# DmxAnalogLed.net
KiCad netlist of a schematic drawn in EAGLE
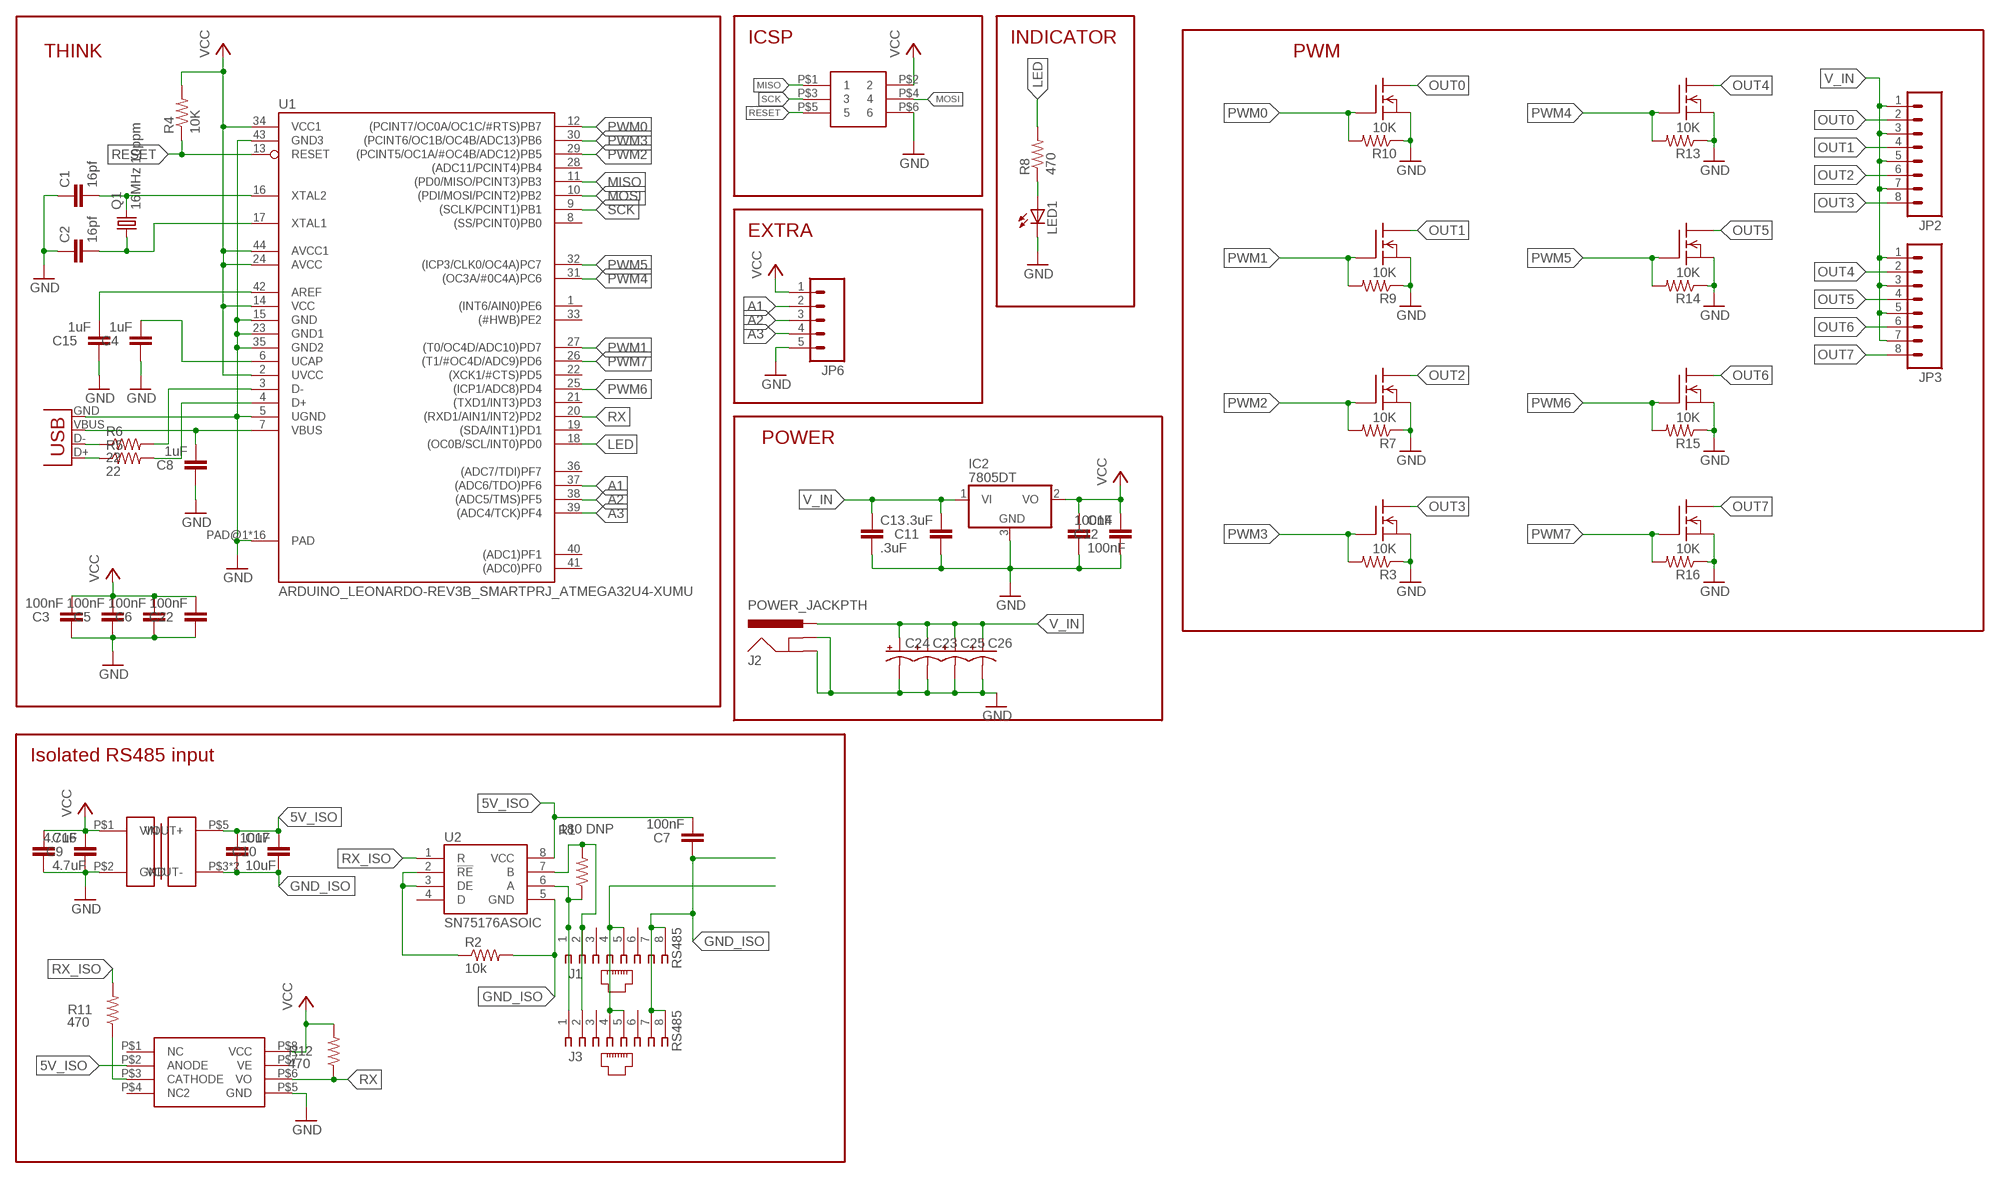
[diagram p0: schematic, sheet 1]

(export (version "E")
  (design (tool "Eeschema 10.0.6"))
  (components
    (comp (ref "C1")
      (value "16pf")
      (footprint "eagle-import:0805")
      (libsource (lib "eagle-import") (part "CAP0805"))
    )
    (comp (ref "C2")
      (value "16pf")
      (footprint "eagle-import:0805")
      (libsource (lib "eagle-import") (part "CAP0805"))
    )
    (comp (ref "C3")
      (value "100nF")
      (footprint "eagle-import:0805")
      (libsource (lib "eagle-import") (part "CAP0805"))
    )
    (comp (ref "C4")
      (value "1uF")
      (footprint "eagle-import:0805")
      (libsource (lib "eagle-import") (part "CAP0805"))
    )
    (comp (ref "C5")
      (value "100nF")
      (footprint "eagle-import:0805")
      (libsource (lib "eagle-import") (part "CAP0805"))
    )
    (comp (ref "C6")
      (value "100nF")
      (footprint "eagle-import:0805")
      (libsource (lib "eagle-import") (part "CAP0805"))
    )
    (comp (ref "C7")
      (value "100nF")
      (footprint "eagle-import:0805")
      (libsource (lib "eagle-import") (part "CAP0805"))
    )
    (comp (ref "C8")
      (value "1uF")
      (footprint "eagle-import:0805")
      (libsource (lib "eagle-import") (part "CAP0805"))
    )
    (comp (ref "C9")
      (value "4.7uF")
      (footprint "eagle-import:0805")
      (libsource (lib "eagle-import") (part "CAP0805"))
    )
    (comp (ref "C10")
      (value "10uF")
      (footprint "eagle-import:0805")
      (libsource (lib "eagle-import") (part "CAP0805"))
    )
    (comp (ref "C11")
      (value ".3uF")
      (footprint "eagle-import:0805")
      (libsource (lib "eagle-import") (part "CAP0805"))
    )
    (comp (ref "C12")
      (value "100nF")
      (footprint "eagle-import:0805")
      (libsource (lib "eagle-import") (part "CAP0805"))
    )
    (comp (ref "C13")
      (value ".3uF")
      (footprint "eagle-import:1210")
      (libsource (lib "eagle-import") (part "CAP1210"))
    )
    (comp (ref "C14")
      (value "100nF")
      (footprint "eagle-import:1210")
      (libsource (lib "eagle-import") (part "CAP1210"))
    )
    (comp (ref "C15")
      (value "1uF")
      (footprint "eagle-import:0805")
      (libsource (lib "eagle-import") (part "CAP0805"))
    )
    (comp (ref "C16")
      (value "4.7uF")
      (footprint "eagle-import:1210")
      (libsource (lib "eagle-import") (part "CAP1210"))
    )
    (comp (ref "C17")
      (value "10uF")
      (footprint "eagle-import:1210")
      (libsource (lib "eagle-import") (part "CAP1210"))
    )
    (comp (ref "C22")
      (value "100nF")
      (footprint "eagle-import:0805")
      (libsource (lib "eagle-import") (part "CAP0805"))
    )
    (comp (ref "C23")
      (value "CAP_POLE")
      (footprint "eagle-import:PANASONIC_E")
      (libsource (lib "eagle-import") (part "CAP_POLE"))
    )
    (comp (ref "C24")
      (value "CAP_POLE")
      (footprint "eagle-import:PANASONIC_E")
      (libsource (lib "eagle-import") (part "CAP_POLE"))
    )
    (comp (ref "C25")
      (value "CAP_POLE")
      (footprint "eagle-import:PANASONIC_E")
      (libsource (lib "eagle-import") (part "CAP_POLE"))
    )
    (comp (ref "C26")
      (value "CAP_POLE")
      (footprint "eagle-import:PANASONIC_E")
      (libsource (lib "eagle-import") (part "CAP_POLE"))
    )
    (comp (ref "IC2")
      (value "7805DT")
      (footprint "eagle-import:TO252")
      (libsource (lib "eagle-import") (part "78DT05"))
    )
    (comp (ref "J1")
      (value "RS485")
      (footprint "eagle-import:520426-4")
      (libsource (lib "eagle-import") (part "520426-4"))
    )
    (comp (ref "J2")
      (value "POWER_JACKPTH")
      (footprint "eagle-import:POWER_JACK_PTH")
      (libsource (lib "eagle-import") (part "POWER_JACKPTH"))
    )
    (comp (ref "J3")
      (value "RS485")
      (footprint "eagle-import:520426-4")
      (libsource (lib "eagle-import") (part "520426-4"))
    )
    (comp (ref "JP2")
      (value "M083.5MM-8")
      (footprint "eagle-import:SCREWTERMINAL-3.5MM-8")
      (libsource (lib "eagle-import") (part "M083.5MM-8"))
    )
    (comp (ref "JP3")
      (value "M083.5MM-8")
      (footprint "eagle-import:SCREWTERMINAL-3.5MM-8")
      (libsource (lib "eagle-import") (part "M083.5MM-8"))
    )
    (comp (ref "JP6")
      (value "M05PTH")
      (footprint "eagle-import:1X05")
      (libsource (lib "eagle-import") (part "M05PTH"))
    )
    (comp (ref "LED1")
      (value "LED5MM")
      (footprint "eagle-import:LED5MM")
      (libsource (lib "eagle-import") (part "LED5MM"))
    )
    (comp (ref "Q1")
      (value "16MHz 10ppm")
      (footprint "eagle-import:XS3225")
      (libsource (lib "eagle-import") (part "CRYSTAL"))
    )
    (comp (ref "R1")
      (value "180 DNP")
      (footprint "eagle-import:0805")
      (libsource (lib "eagle-import") (part "RESISTOR"))
    )
    (comp (ref "R2")
      (value "10k")
      (footprint "eagle-import:0805")
      (libsource (lib "eagle-import") (part "RESISTOR"))
    )
    (comp (ref "R3")
      (value "10K")
      (footprint "eagle-import:0805")
      (libsource (lib "eagle-import") (part "RESISTOR"))
    )
    (comp (ref "R4")
      (value "10K")
      (footprint "eagle-import:0805")
      (libsource (lib "eagle-import") (part "RESISTOR"))
    )
    (comp (ref "R5")
      (value "22")
      (footprint "eagle-import:0805")
      (libsource (lib "eagle-import") (part "RESISTOR"))
    )
    (comp (ref "R6")
      (value "22")
      (footprint "eagle-import:0805")
      (libsource (lib "eagle-import") (part "RESISTOR"))
    )
    (comp (ref "R7")
      (value "10K")
      (footprint "eagle-import:0805")
      (libsource (lib "eagle-import") (part "RESISTOR"))
    )
    (comp (ref "R8")
      (value "470")
      (footprint "eagle-import:0805")
      (libsource (lib "eagle-import") (part "RESISTOR"))
    )
    (comp (ref "R9")
      (value "10K")
      (footprint "eagle-import:0805")
      (libsource (lib "eagle-import") (part "RESISTOR"))
    )
    (comp (ref "R10")
      (value "10K")
      (footprint "eagle-import:0805")
      (libsource (lib "eagle-import") (part "RESISTOR"))
    )
    (comp (ref "R11")
      (value "470")
      (footprint "eagle-import:0805")
      (libsource (lib "eagle-import") (part "RESISTOR"))
    )
    (comp (ref "R12")
      (value "470")
      (footprint "eagle-import:0805")
      (libsource (lib "eagle-import") (part "RESISTOR"))
    )
    (comp (ref "R13")
      (value "10K")
      (footprint "eagle-import:0805")
      (libsource (lib "eagle-import") (part "RESISTOR"))
    )
    (comp (ref "R14")
      (value "10K")
      (footprint "eagle-import:0805")
      (libsource (lib "eagle-import") (part "RESISTOR"))
    )
    (comp (ref "R15")
      (value "10K")
      (footprint "eagle-import:0805")
      (libsource (lib "eagle-import") (part "RESISTOR"))
    )
    (comp (ref "R16")
      (value "10K")
      (footprint "eagle-import:0805")
      (libsource (lib "eagle-import") (part "RESISTOR"))
    )
    (comp (ref "U$1")
      (value "N_MOSFET")
      (footprint "eagle-import:TO252")
      (libsource (lib "eagle-import") (part "N_MOSFET"))
    )
    (comp (ref "U$2")
      (value "2X3HEADER")
      (footprint "eagle-import:2X3HEADER")
      (libsource (lib "eagle-import") (part "2X3HEADER"))
    )
    (comp (ref "U$3")
      (value "N_MOSFET")
      (footprint "eagle-import:TO252")
      (libsource (lib "eagle-import") (part "N_MOSFET"))
    )
    (comp (ref "U$4")
      (value "N_MOSFET")
      (footprint "eagle-import:TO252")
      (libsource (lib "eagle-import") (part "N_MOSFET"))
    )
    (comp (ref "U$5")
      (value "N_MOSFET")
      (footprint "eagle-import:TO252")
      (libsource (lib "eagle-import") (part "N_MOSFET"))
    )
    (comp (ref "U$6")
      (value "N_MOSFET")
      (footprint "eagle-import:TO252")
      (libsource (lib "eagle-import") (part "N_MOSFET"))
    )
    (comp (ref "U$7")
      (value "N_MOSFET")
      (footprint "eagle-import:TO252")
      (libsource (lib "eagle-import") (part "N_MOSFET"))
    )
    (comp (ref "U$8")
      (value "N_MOSFET")
      (footprint "eagle-import:TO252")
      (libsource (lib "eagle-import") (part "N_MOSFET"))
    )
    (comp (ref "U$9")
      (value "N_MOSFET")
      (footprint "eagle-import:TO252")
      (libsource (lib "eagle-import") (part "N_MOSFET"))
    )
    (comp (ref "U$10")
      (value "DC_DC_ISOLATED_0505")
      (footprint "eagle-import:IB_XLS-1W")
      (libsource (lib "eagle-import") (part "DC_DC_ISOLATED_0505"))
    )
    (comp (ref "U$12")
      (value "6N137")
      (footprint "eagle-import:8_SOIC")
      (libsource (lib "eagle-import") (part "6N137"))
    )
    (comp (ref "U1")
      (value "ARDUINO_LEONARDO-REV3B_SMARTPRJ_ATMEGA32U4-XUMU")
      (footprint "eagle-import:ARDUINO_LEONARDO-REV3B_SMARTPRJ_QFN44ML7X7")
      (libsource (lib "eagle-import") (part "ARDUINO_LEONARDO-REV3B_SMARTPRJ_ATMEGA32U4-XUMU"))
    )
    (comp (ref "U2")
      (value "SN75176ASOIC")
      (footprint "eagle-import:SO08")
      (libsource (lib "eagle-import") (part "SN75176ASOIC"))
    )
    (comp (ref "X1")
      (value "USBPTH")
      (footprint "eagle-import:USB-B-PTH")
      (libsource (lib "eagle-import") (part "USBPTH"))
    )
  )
  (nets
    (net (code "1") (name "5V_ISO") (class "Default")
      (node (ref "C10") (pin "2") (pinfunction "2_2") (pintype "passive"))
      (node (ref "C17") (pin "1") (pinfunction "1_1") (pintype "passive"))
      (node (ref "C7") (pin "2") (pinfunction "2_2") (pintype "passive"))
      (node (ref "U$10") (pin "P$5") (pinfunction "VOUT+_P$5") (pintype "power_in"))
      (node (ref "U$12") (pin "P$2") (pinfunction "ANODE_P$2") (pintype "bidirectional"))
      (node (ref "U2") (pin "8") (pinfunction "VCC_8") (pintype "bidirectional"))
    )
    (net (code "2") (name "A1") (class "Default")
      (node (ref "JP6") (pin "2") (pinfunction "2_2") (pintype "passive"))
      (node (ref "U1") (pin "37") (pinfunction "(ADC6/TDO)PF6_37") (pintype "bidirectional"))
    )
    (net (code "3") (name "A2") (class "Default")
      (node (ref "JP6") (pin "3") (pinfunction "3_3") (pintype "passive"))
      (node (ref "U1") (pin "38") (pinfunction "(ADC5/TMS)PF5_38") (pintype "bidirectional"))
    )
    (net (code "4") (name "A3") (class "Default")
      (node (ref "JP6") (pin "4") (pinfunction "4_4") (pintype "passive"))
      (node (ref "U1") (pin "39") (pinfunction "(ADC4/TCK)PF4_39") (pintype "bidirectional"))
    )
    (net (code "5") (name "GND") (class "Default")
      (node (ref "C1") (pin "1") (pinfunction "1_1") (pintype "passive"))
      (node (ref "C11") (pin "1") (pinfunction "1_1") (pintype "passive"))
      (node (ref "C12") (pin "1") (pinfunction "1_1") (pintype "passive"))
      (node (ref "C13") (pin "2") (pinfunction "2_2") (pintype "passive"))
      (node (ref "C14") (pin "2") (pinfunction "2_2") (pintype "passive"))
      (node (ref "C15") (pin "1") (pinfunction "1_1") (pintype "passive"))
      (node (ref "C16") (pin "2") (pinfunction "2_2") (pintype "passive"))
      (node (ref "C2") (pin "1") (pinfunction "1_1") (pintype "passive"))
      (node (ref "C22") (pin "1") (pinfunction "1_1") (pintype "passive"))
      (node (ref "C23") (pin "-") (pinfunction "-_-") (pintype "passive"))
      (node (ref "C24") (pin "-") (pinfunction "-_-") (pintype "passive"))
      (node (ref "C25") (pin "-") (pinfunction "-_-") (pintype "passive"))
      (node (ref "C26") (pin "-") (pinfunction "-_-") (pintype "passive"))
      (node (ref "C3") (pin "1") (pinfunction "1_1") (pintype "passive"))
      (node (ref "C4") (pin "1") (pinfunction "1_1") (pintype "passive"))
      (node (ref "C5") (pin "1") (pinfunction "1_1") (pintype "passive"))
      (node (ref "C6") (pin "1") (pinfunction "1_1") (pintype "passive"))
      (node (ref "C8") (pin "1") (pinfunction "1_1") (pintype "passive"))
      (node (ref "C9") (pin "1") (pinfunction "1_1") (pintype "passive"))
      (node (ref "IC2") (pin "3") (pinfunction "GND_3") (pintype "passive"))
      (node (ref "J2") (pin "GND") (pinfunction "GND_GND") (pintype "bidirectional"))
      (node (ref "J2") (pin "GNDBREAK") (pinfunction "GNDBREAK_GNDBREAK") (pintype "bidirectional"))
      (node (ref "JP6") (pin "5") (pinfunction "5_5") (pintype "passive"))
      (node (ref "LED1") (pin "K") (pinfunction "C_K") (pintype "passive"))
      (node (ref "R10") (pin "1") (pinfunction "1_1") (pintype "passive"))
      (node (ref "R13") (pin "1") (pinfunction "1_1") (pintype "passive"))
      (node (ref "R14") (pin "1") (pinfunction "1_1") (pintype "passive"))
      (node (ref "R15") (pin "1") (pinfunction "1_1") (pintype "passive"))
      (node (ref "R16") (pin "1") (pinfunction "1_1") (pintype "passive"))
      (node (ref "R3") (pin "1") (pinfunction "1_1") (pintype "passive"))
      (node (ref "R7") (pin "1") (pinfunction "1_1") (pintype "passive"))
      (node (ref "R9") (pin "1") (pinfunction "1_1") (pintype "passive"))
      (node (ref "U$1") (pin "P$2") (pinfunction "S_P$2") (pintype "bidirectional"))
      (node (ref "U$10") (pin "P$2") (pinfunction "GND_P$2") (pintype "power_in"))
      (node (ref "U$12") (pin "P$5") (pinfunction "GND_P$5") (pintype "bidirectional"))
      (node (ref "U$2") (pin "P$6") (pinfunction "6_P$6") (pintype "bidirectional"))
      (node (ref "U$3") (pin "P$2") (pinfunction "S_P$2") (pintype "bidirectional"))
      (node (ref "U$4") (pin "P$2") (pinfunction "S_P$2") (pintype "bidirectional"))
      (node (ref "U$5") (pin "P$2") (pinfunction "S_P$2") (pintype "bidirectional"))
      (node (ref "U$6") (pin "P$2") (pinfunction "S_P$2") (pintype "bidirectional"))
      (node (ref "U$7") (pin "P$2") (pinfunction "S_P$2") (pintype "bidirectional"))
      (node (ref "U$8") (pin "P$2") (pinfunction "S_P$2") (pintype "bidirectional"))
      (node (ref "U$9") (pin "P$2") (pinfunction "S_P$2") (pintype "bidirectional"))
      (node (ref "U1") (pin "15") (pinfunction "GND_15") (pintype "power_in"))
      (node (ref "U1") (pin "23") (pinfunction "GND1_23") (pintype "power_in"))
      (node (ref "U1") (pin "35") (pinfunction "GND2_35") (pintype "power_in"))
      (node (ref "U1") (pin "43") (pinfunction "GND3_43") (pintype "power_in"))
      (node (ref "U1") (pin "5") (pinfunction "UGND_5") (pintype "power_in"))
      (node (ref "U1") (pin "PAD@1") (pinfunction "PAD_PAD@1") (pintype "power_in"))
      (node (ref "U1") (pin "PAD@10") (pinfunction "PAD_PAD@10") (pintype "power_in"))
      (node (ref "U1") (pin "PAD@11") (pinfunction "PAD_PAD@11") (pintype "power_in"))
      (node (ref "U1") (pin "PAD@12") (pinfunction "PAD_PAD@12") (pintype "power_in"))
      (node (ref "U1") (pin "PAD@13") (pinfunction "PAD_PAD@13") (pintype "power_in"))
      (node (ref "U1") (pin "PAD@14") (pinfunction "PAD_PAD@14") (pintype "power_in"))
      (node (ref "U1") (pin "PAD@15") (pinfunction "PAD_PAD@15") (pintype "power_in"))
      (node (ref "U1") (pin "PAD@16") (pinfunction "PAD_PAD@16") (pintype "power_in"))
      (node (ref "U1") (pin "PAD@2") (pinfunction "PAD_PAD@2") (pintype "power_in"))
      (node (ref "U1") (pin "PAD@3") (pinfunction "PAD_PAD@3") (pintype "power_in"))
      (node (ref "U1") (pin "PAD@4") (pinfunction "PAD_PAD@4") (pintype "power_in"))
      (node (ref "U1") (pin "PAD@5") (pinfunction "PAD_PAD@5") (pintype "power_in"))
      (node (ref "U1") (pin "PAD@6") (pinfunction "PAD_PAD@6") (pintype "power_in"))
      (node (ref "U1") (pin "PAD@7") (pinfunction "PAD_PAD@7") (pintype "power_in"))
      (node (ref "U1") (pin "PAD@8") (pinfunction "PAD_PAD@8") (pintype "power_in"))
      (node (ref "U1") (pin "PAD@9") (pinfunction "PAD_PAD@9") (pintype "power_in"))
      (node (ref "X1") (pin "GND") (pinfunction "GND_GND") (pintype "bidirectional"))
    )
    (net (code "6") (name "GND_ISO") (class "Default")
      (node (ref "C10") (pin "1") (pinfunction "1_1") (pintype "passive"))
      (node (ref "C17") (pin "2") (pinfunction "2_2") (pintype "passive"))
      (node (ref "C7") (pin "1") (pinfunction "1_1") (pintype "passive"))
      (node (ref "J1") (pin "7") (pinfunction "7_7") (pintype "passive"))
      (node (ref "J1") (pin "8") (pinfunction "8_8") (pintype "passive"))
      (node (ref "J3") (pin "7") (pinfunction "7_7") (pintype "passive"))
      (node (ref "J3") (pin "8") (pinfunction "8_8") (pintype "passive"))
      (node (ref "R2") (pin "2") (pinfunction "2_2") (pintype "passive"))
      (node (ref "U$10") (pin "P$3") (pinfunction "VOUT-_P$3") (pintype "power_in"))
      (node (ref "U$10") (pin "P$4") (pinfunction "VOUT-_P$4") (pintype "power_in"))
      (node (ref "U2") (pin "5") (pinfunction "GND_5") (pintype "bidirectional"))
    )
    (net (code "7") (name "LED") (class "Default")
      (node (ref "R8") (pin "2") (pinfunction "2_2") (pintype "passive"))
      (node (ref "U1") (pin "18") (pinfunction "(OC0B/SCL/INT0)PD0_18") (pintype "bidirectional"))
    )
    (net (code "8") (name "MISO") (class "Default")
      (node (ref "U$2") (pin "P$1") (pinfunction "1_P$1") (pintype "bidirectional"))
      (node (ref "U1") (pin "11") (pinfunction "(PD0/MISO/PCINT3)PB3_11") (pintype "bidirectional"))
    )
    (net (code "9") (name "MOSI") (class "Default")
      (node (ref "U$2") (pin "P$4") (pinfunction "4_P$4") (pintype "bidirectional"))
      (node (ref "U1") (pin "10") (pinfunction "(PDI/MOSI/PCINT2)PB2_10") (pintype "bidirectional"))
    )
    (net (code "10") (name "Net-(J1-Pad4)") (class "Default")
      (node (ref "J1") (pin "4") (pinfunction "4_4") (pintype "passive"))
      (node (ref "J1") (pin "5") (pinfunction "5_5") (pintype "passive"))
      (node (ref "J3") (pin "4") (pinfunction "4_4") (pintype "passive"))
      (node (ref "J3") (pin "5") (pinfunction "5_5") (pintype "passive"))
    )
    (net (code "11") (name "Net-(LED1-PadA)") (class "Default")
      (node (ref "LED1") (pin "A") (pinfunction "A_A") (pintype "passive"))
      (node (ref "R8") (pin "1") (pinfunction "1_1") (pintype "passive"))
    )
    (net (code "12") (name "Net-(Q1-1)") (class "Default")
      (node (ref "C2") (pin "2") (pinfunction "2_2") (pintype "passive"))
      (node (ref "Q1") (pin "P$1") (pinfunction "1_P$1") (pintype "passive"))
      (node (ref "U1") (pin "17") (pinfunction "XTAL1_17") (pintype "bidirectional"))
    )
    (net (code "13") (name "Net-(Q1-2)") (class "Default")
      (node (ref "C1") (pin "2") (pinfunction "2_2") (pintype "passive"))
      (node (ref "Q1") (pin "P$3") (pinfunction "2_P$3") (pintype "passive"))
      (node (ref "U1") (pin "16") (pinfunction "XTAL2_16") (pintype "bidirectional"))
    )
    (net (code "14") (name "Net-(R5-Pad1)") (class "Default")
      (node (ref "R5") (pin "1") (pinfunction "1_1") (pintype "passive"))
      (node (ref "X1") (pin "D+") (pinfunction "D+_D+") (pintype "bidirectional"))
    )
    (net (code "15") (name "Net-(R6-Pad1)") (class "Default")
      (node (ref "R6") (pin "1") (pinfunction "1_1") (pintype "passive"))
      (node (ref "X1") (pin "D-") (pinfunction "D-_D-") (pintype "bidirectional"))
    )
    (net (code "16") (name "Net-(U$12-CATHODE)") (class "Default")
      (node (ref "R11") (pin "1") (pinfunction "1_1") (pintype "passive"))
      (node (ref "U$12") (pin "P$3") (pinfunction "CATHODE_P$3") (pintype "bidirectional"))
    )
    (net (code "17") (name "Net-(U1-AREF)") (class "Default")
      (node (ref "C15") (pin "2") (pinfunction "2_2") (pintype "passive"))
      (node (ref "U1") (pin "42") (pinfunction "AREF_42") (pintype "power_in"))
    )
    (net (code "18") (name "Net-(U1-D+)") (class "Default")
      (node (ref "R5") (pin "2") (pinfunction "2_2") (pintype "passive"))
      (node (ref "U1") (pin "4") (pinfunction "D+_4") (pintype "bidirectional"))
    )
    (net (code "19") (name "Net-(U1-D-)") (class "Default")
      (node (ref "R6") (pin "2") (pinfunction "2_2") (pintype "passive"))
      (node (ref "U1") (pin "3") (pinfunction "D-_3") (pintype "bidirectional"))
    )
    (net (code "20") (name "Net-(U1-UCAP)") (class "Default")
      (node (ref "C4") (pin "2") (pinfunction "2_2") (pintype "passive"))
      (node (ref "U1") (pin "6") (pinfunction "UCAP_6") (pintype "passive"))
    )
    (net (code "21") (name "Net-(U1-VBUS)") (class "Default")
      (node (ref "C8") (pin "2") (pinfunction "2_2") (pintype "passive"))
      (node (ref "U1") (pin "7") (pinfunction "VBUS_7") (pintype "input"))
      (node (ref "X1") (pin "VBUS") (pinfunction "VBUS_VBUS") (pintype "bidirectional"))
    )
    (net (code "22") (name "Net-(U2-A)") (class "Default")
      (node (ref "J1") (pin "1") (pinfunction "1_1") (pintype "passive"))
      (node (ref "J3") (pin "1") (pinfunction "1_1") (pintype "passive"))
      (node (ref "R1") (pin "1") (pinfunction "1_1") (pintype "passive"))
      (node (ref "U2") (pin "6") (pinfunction "A_6") (pintype "bidirectional"))
    )
    (net (code "23") (name "Net-(U2-B)") (class "Default")
      (node (ref "J1") (pin "2") (pinfunction "2_2") (pintype "passive"))
      (node (ref "J3") (pin "2") (pinfunction "2_2") (pintype "passive"))
      (node (ref "R1") (pin "2") (pinfunction "2_2") (pintype "passive"))
      (node (ref "U2") (pin "7") (pinfunction "B_7") (pintype "bidirectional"))
    )
    (net (code "24") (name "Net-(U2-DE)") (class "Default")
      (node (ref "R2") (pin "1") (pinfunction "1_1") (pintype "passive"))
      (node (ref "U2") (pin "2") (pinfunction "~{RE}_2") (pintype "bidirectional"))
      (node (ref "U2") (pin "3") (pinfunction "DE_3") (pintype "bidirectional"))
    )
    (net (code "25") (name "OUT0") (class "Default")
      (node (ref "JP2") (pin "2") (pinfunction "2_2") (pintype "passive"))
      (node (ref "U$1") (pin "P$3") (pinfunction "D_P$3") (pintype "bidirectional"))
    )
    (net (code "26") (name "OUT1") (class "Default")
      (node (ref "JP2") (pin "4") (pinfunction "4_4") (pintype "passive"))
      (node (ref "U$3") (pin "P$3") (pinfunction "D_P$3") (pintype "bidirectional"))
    )
    (net (code "27") (name "OUT2") (class "Default")
      (node (ref "JP2") (pin "6") (pinfunction "6_6") (pintype "passive"))
      (node (ref "U$4") (pin "P$3") (pinfunction "D_P$3") (pintype "bidirectional"))
    )
    (net (code "28") (name "OUT3") (class "Default")
      (node (ref "JP2") (pin "8") (pinfunction "8_8") (pintype "passive"))
      (node (ref "U$5") (pin "P$3") (pinfunction "D_P$3") (pintype "bidirectional"))
    )
    (net (code "29") (name "OUT4") (class "Default")
      (node (ref "JP3") (pin "2") (pinfunction "2_2") (pintype "passive"))
      (node (ref "U$6") (pin "P$3") (pinfunction "D_P$3") (pintype "bidirectional"))
    )
    (net (code "30") (name "OUT5") (class "Default")
      (node (ref "JP3") (pin "4") (pinfunction "4_4") (pintype "passive"))
      (node (ref "U$7") (pin "P$3") (pinfunction "D_P$3") (pintype "bidirectional"))
    )
    (net (code "31") (name "OUT6") (class "Default")
      (node (ref "JP3") (pin "6") (pinfunction "6_6") (pintype "passive"))
      (node (ref "U$8") (pin "P$3") (pinfunction "D_P$3") (pintype "bidirectional"))
    )
    (net (code "32") (name "OUT7") (class "Default")
      (node (ref "JP3") (pin "8") (pinfunction "8_8") (pintype "passive"))
      (node (ref "U$9") (pin "P$3") (pinfunction "D_P$3") (pintype "bidirectional"))
    )
    (net (code "33") (name "PWM0") (class "Default")
      (node (ref "R10") (pin "2") (pinfunction "2_2") (pintype "passive"))
      (node (ref "U$1") (pin "P$1") (pinfunction "G_P$1") (pintype "bidirectional"))
      (node (ref "U1") (pin "12") (pinfunction "(PCINT7/OC0A/OC1C/#RTS)PB7_12") (pintype "bidirectional"))
    )
    (net (code "34") (name "PWM1") (class "Default")
      (node (ref "R9") (pin "2") (pinfunction "2_2") (pintype "passive"))
      (node (ref "U$3") (pin "P$1") (pinfunction "G_P$1") (pintype "bidirectional"))
      (node (ref "U1") (pin "27") (pinfunction "(T0/OC4D/ADC10)PD7_27") (pintype "bidirectional"))
    )
    (net (code "35") (name "PWM2") (class "Default")
      (node (ref "R7") (pin "2") (pinfunction "2_2") (pintype "passive"))
      (node (ref "U$4") (pin "P$1") (pinfunction "G_P$1") (pintype "bidirectional"))
      (node (ref "U1") (pin "29") (pinfunction "(PCINT5/OC1A/#OC4B/ADC12)PB5_29") (pintype "bidirectional"))
    )
    (net (code "36") (name "PWM3") (class "Default")
      (node (ref "R3") (pin "2") (pinfunction "2_2") (pintype "passive"))
      (node (ref "U$5") (pin "P$1") (pinfunction "G_P$1") (pintype "bidirectional"))
      (node (ref "U1") (pin "30") (pinfunction "(PCINT6/OC1B/OC4B/ADC13)PB6_30") (pintype "bidirectional"))
    )
    (net (code "37") (name "PWM4") (class "Default")
      (node (ref "R13") (pin "2") (pinfunction "2_2") (pintype "passive"))
      (node (ref "U$6") (pin "P$1") (pinfunction "G_P$1") (pintype "bidirectional"))
      (node (ref "U1") (pin "31") (pinfunction "(OC3A/#0C4A)PC6_31") (pintype "bidirectional"))
    )
    (net (code "38") (name "PWM5") (class "Default")
      (node (ref "R14") (pin "2") (pinfunction "2_2") (pintype "passive"))
      (node (ref "U$7") (pin "P$1") (pinfunction "G_P$1") (pintype "bidirectional"))
      (node (ref "U1") (pin "32") (pinfunction "(ICP3/CLK0/OC4A)PC7_32") (pintype "bidirectional"))
    )
    (net (code "39") (name "PWM6") (class "Default")
      (node (ref "R15") (pin "2") (pinfunction "2_2") (pintype "passive"))
      (node (ref "U$8") (pin "P$1") (pinfunction "G_P$1") (pintype "bidirectional"))
      (node (ref "U1") (pin "25") (pinfunction "(ICP1/ADC8)PD4_25") (pintype "bidirectional"))
    )
    (net (code "40") (name "PWM7") (class "Default")
      (node (ref "R16") (pin "2") (pinfunction "2_2") (pintype "passive"))
      (node (ref "U$9") (pin "P$1") (pinfunction "G_P$1") (pintype "bidirectional"))
      (node (ref "U1") (pin "26") (pinfunction "(T1/#OC4D/ADC9)PD6_26") (pintype "bidirectional"))
    )
    (net (code "41") (name "RESET") (class "Default")
      (node (ref "R4") (pin "1") (pinfunction "1_1") (pintype "passive"))
      (node (ref "U$2") (pin "P$5") (pinfunction "5_P$5") (pintype "bidirectional"))
      (node (ref "U1") (pin "13") (pinfunction "RESET_13") (pintype "input"))
    )
    (net (code "42") (name "RX") (class "Default")
      (node (ref "R12") (pin "1") (pinfunction "1_1") (pintype "passive"))
      (node (ref "U$12") (pin "P$6") (pinfunction "VO_P$6") (pintype "bidirectional"))
      (node (ref "U1") (pin "20") (pinfunction "(RXD1/AIN1/INT2)PD2_20") (pintype "bidirectional"))
    )
    (net (code "43") (name "RX_ISO") (class "Default")
      (node (ref "R11") (pin "2") (pinfunction "2_2") (pintype "passive"))
      (node (ref "U2") (pin "1") (pinfunction "R_1") (pintype "bidirectional"))
    )
    (net (code "44") (name "SCK") (class "Default")
      (node (ref "U$2") (pin "P$3") (pinfunction "3_P$3") (pintype "bidirectional"))
      (node (ref "U1") (pin "9") (pinfunction "(SCLK/PCINT1)PB1_9") (pintype "bidirectional"))
    )
    (net (code "45") (name "VCC") (class "Default")
      (node (ref "C12") (pin "2") (pinfunction "2_2") (pintype "passive"))
      (node (ref "C14") (pin "1") (pinfunction "1_1") (pintype "passive"))
      (node (ref "C16") (pin "1") (pinfunction "1_1") (pintype "passive"))
      (node (ref "C22") (pin "2") (pinfunction "2_2") (pintype "passive"))
      (node (ref "C3") (pin "2") (pinfunction "2_2") (pintype "passive"))
      (node (ref "C5") (pin "2") (pinfunction "2_2") (pintype "passive"))
      (node (ref "C6") (pin "2") (pinfunction "2_2") (pintype "passive"))
      (node (ref "C9") (pin "2") (pinfunction "2_2") (pintype "passive"))
      (node (ref "IC2") (pin "2") (pinfunction "VO_2") (pintype "passive"))
      (node (ref "JP6") (pin "1") (pinfunction "1_1") (pintype "passive"))
      (node (ref "R12") (pin "2") (pinfunction "2_2") (pintype "passive"))
      (node (ref "R4") (pin "2") (pinfunction "2_2") (pintype "passive"))
      (node (ref "U$10") (pin "P$1") (pinfunction "VIN_P$1") (pintype "power_in"))
      (node (ref "U$12") (pin "P$8") (pinfunction "VCC_P$8") (pintype "bidirectional"))
      (node (ref "U$2") (pin "P$2") (pinfunction "2_P$2") (pintype "bidirectional"))
      (node (ref "U1") (pin "14") (pinfunction "VCC_14") (pintype "power_in"))
      (node (ref "U1") (pin "2") (pinfunction "UVCC_2") (pintype "power_in"))
      (node (ref "U1") (pin "24") (pinfunction "AVCC_24") (pintype "power_in"))
      (node (ref "U1") (pin "34") (pinfunction "VCC1_34") (pintype "power_in"))
      (node (ref "U1") (pin "44") (pinfunction "AVCC1_44") (pintype "power_in"))
    )
    (net (code "46") (name "V_IN") (class "Default")
      (node (ref "C11") (pin "2") (pinfunction "2_2") (pintype "passive"))
      (node (ref "C13") (pin "1") (pinfunction "1_1") (pintype "passive"))
      (node (ref "C23") (pin "+") (pinfunction "+_+") (pintype "passive"))
      (node (ref "C24") (pin "+") (pinfunction "+_+") (pintype "passive"))
      (node (ref "C25") (pin "+") (pinfunction "+_+") (pintype "passive"))
      (node (ref "C26") (pin "+") (pinfunction "+_+") (pintype "passive"))
      (node (ref "IC2") (pin "1") (pinfunction "VI_1") (pintype "input"))
      (node (ref "J2") (pin "PWR") (pinfunction "PWR_PWR") (pintype "bidirectional"))
      (node (ref "JP2") (pin "1") (pinfunction "1_1") (pintype "passive"))
      (node (ref "JP2") (pin "3") (pinfunction "3_3") (pintype "passive"))
      (node (ref "JP2") (pin "5") (pinfunction "5_5") (pintype "passive"))
      (node (ref "JP2") (pin "7") (pinfunction "7_7") (pintype "passive"))
      (node (ref "JP3") (pin "1") (pinfunction "1_1") (pintype "passive"))
      (node (ref "JP3") (pin "3") (pinfunction "3_3") (pintype "passive"))
      (node (ref "JP3") (pin "5") (pinfunction "5_5") (pintype "passive"))
      (node (ref "JP3") (pin "7") (pinfunction "7_7") (pintype "passive"))
    )
    (net (code "47") (name "unconnected-(J1-Pad3)") (class "Default")
      (node (ref "J1") (pin "3") (pinfunction "3_3") (pintype "passive"))
    )
    (net (code "48") (name "unconnected-(J1-Pad6)") (class "Default")
      (node (ref "J1") (pin "6") (pinfunction "6_6") (pintype "passive"))
    )
    (net (code "49") (name "unconnected-(J3-Pad3)") (class "Default")
      (node (ref "J3") (pin "3") (pinfunction "3_3") (pintype "passive"))
    )
    (net (code "50") (name "unconnected-(J3-Pad6)") (class "Default")
      (node (ref "J3") (pin "6") (pinfunction "6_6") (pintype "passive"))
    )
    (net (code "51") (name "unconnected-(U$12-NC-PadP$1)") (class "Default")
      (node (ref "U$12") (pin "P$1") (pinfunction "NC_P$1") (pintype "bidirectional"))
    )
    (net (code "52") (name "unconnected-(U$12-NC2-PadP$4)") (class "Default")
      (node (ref "U$12") (pin "P$4") (pinfunction "NC2_P$4") (pintype "bidirectional"))
    )
    (net (code "53") (name "unconnected-(U$12-VE-PadP$7)") (class "Default")
      (node (ref "U$12") (pin "P$7") (pinfunction "VE_P$7") (pintype "bidirectional"))
    )
    (net (code "54") (name "unconnected-(U1-(#HWB)PE2-Pad33)") (class "Default")
      (node (ref "U1") (pin "33") (pinfunction "(#HWB)PE2_33") (pintype "bidirectional"))
    )
    (net (code "55") (name "unconnected-(U1-(ADC0)PF0-Pad41)") (class "Default")
      (node (ref "U1") (pin "41") (pinfunction "(ADC0)PF0_41") (pintype "bidirectional"))
    )
    (net (code "56") (name "unconnected-(U1-(ADC1)PF1-Pad40)") (class "Default")
      (node (ref "U1") (pin "40") (pinfunction "(ADC1)PF1_40") (pintype "bidirectional"))
    )
    (net (code "57") (name "unconnected-(U1-(ADC7{slash}TDI)PF7-Pad36)") (class "Default")
      (node (ref "U1") (pin "36") (pinfunction "(ADC7/TDI)PF7_36") (pintype "bidirectional"))
    )
    (net (code "58") (name "unconnected-(U1-(ADC11{slash}PCINT4)PB4-Pad28)") (class "Default")
      (node (ref "U1") (pin "28") (pinfunction "(ADC11/PCINT4)PB4_28") (pintype "bidirectional"))
    )
    (net (code "59") (name "unconnected-(U1-(INT6{slash}AIN0)PE6-Pad1)") (class "Default")
      (node (ref "U1") (pin "1") (pinfunction "(INT6/AIN0)PE6_1") (pintype "bidirectional"))
    )
    (net (code "60") (name "unconnected-(U1-(SDA{slash}INT1)PD1-Pad19)") (class "Default")
      (node (ref "U1") (pin "19") (pinfunction "(SDA/INT1)PD1_19") (pintype "bidirectional"))
    )
    (net (code "61") (name "unconnected-(U1-(SS{slash}PCINT0)PB0-Pad8)") (class "Default")
      (node (ref "U1") (pin "8") (pinfunction "(SS/PCINT0)PB0_8") (pintype "bidirectional"))
    )
    (net (code "62") (name "unconnected-(U1-(TXD1{slash}INT3)PD3-Pad21)") (class "Default")
      (node (ref "U1") (pin "21") (pinfunction "(TXD1/INT3)PD3_21") (pintype "bidirectional"))
    )
    (net (code "63") (name "unconnected-(U1-(XCK1{slash}#CTS)PD5-Pad22)") (class "Default")
      (node (ref "U1") (pin "22") (pinfunction "(XCK1/#CTS)PD5_22") (pintype "bidirectional"))
    )
    (net (code "64") (name "unconnected-(U2-D-Pad4)") (class "Default")
      (node (ref "U2") (pin "4") (pinfunction "D_4") (pintype "bidirectional"))
    )
  )
)
